# schematic.net
KiCad netlist of a schematic drawn in Altium Designer
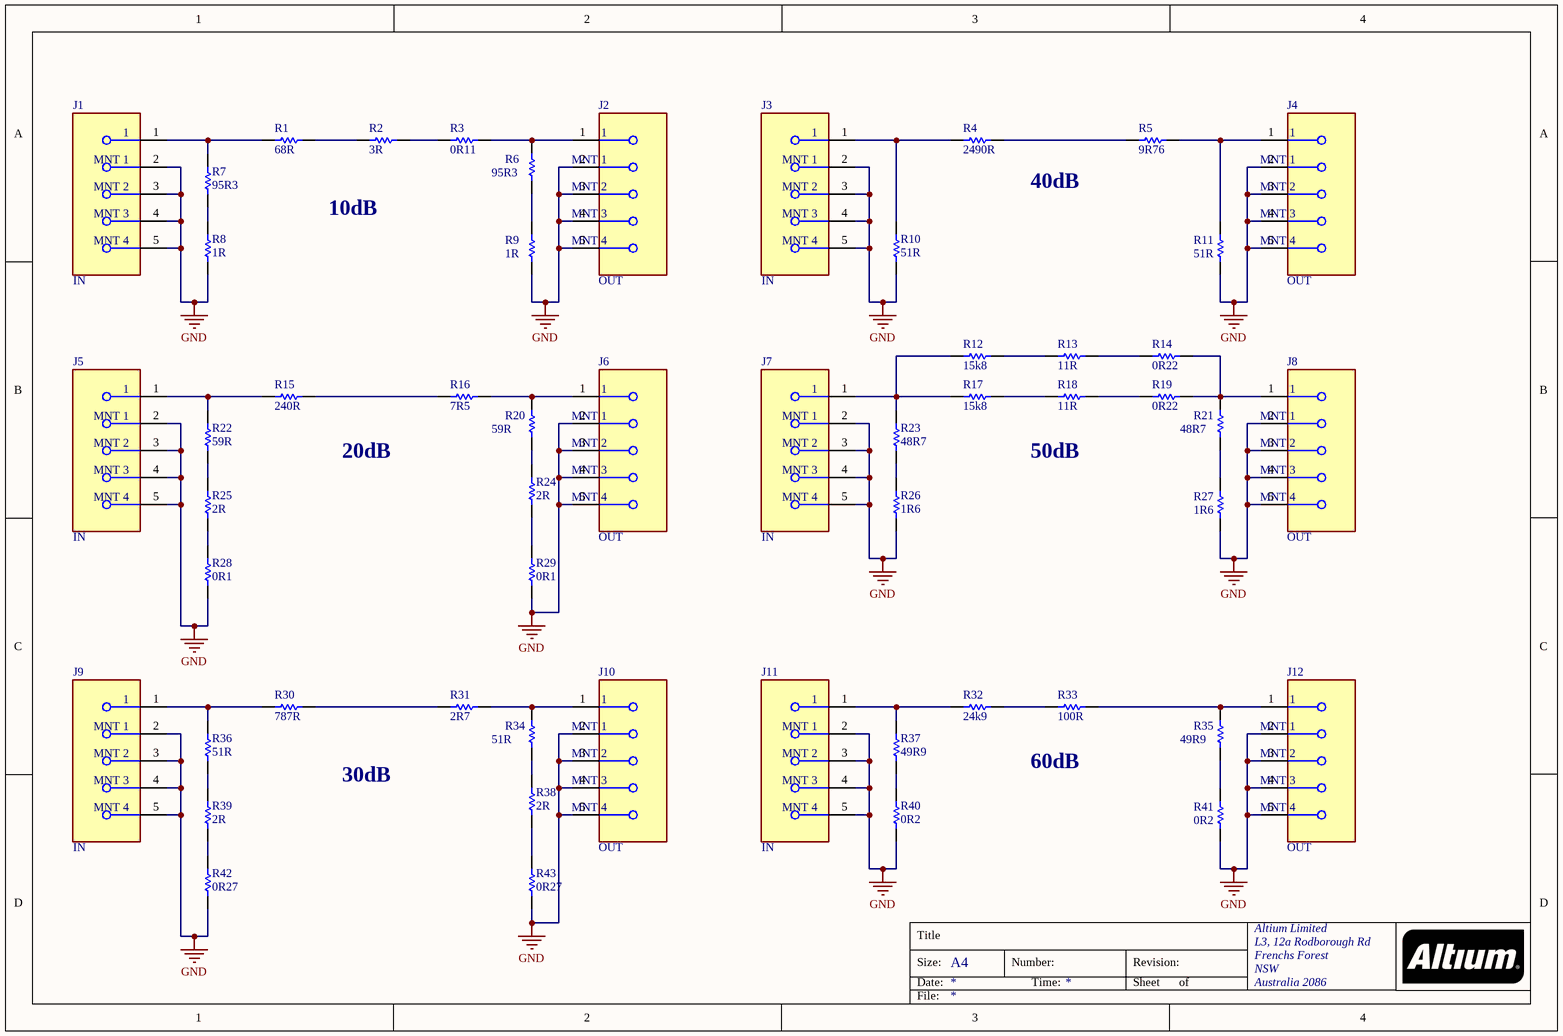
[diagram p0: schematic.SchDoc]

(export (version "E")
  (design (tool "Eeschema 10.0.6"))
  (components
    (comp (ref "J1")
      (value "IN")
      (footprint "FP-CON-SMA-EDGE-S-MFG")
      (description "CONN SMA JACK STR EDGE MNT")
      (fields
        (field (name "OCTOPART") "https://octopart.com/con-sma-edge-s-rf+solutions-70967450")
        (field (name "MANUFACTURER PART NUMBER") "CON-SMA-EDGE-S")
      )
      (libsource (lib "Altium Content Vault") (part "a163d97a771fcdd2fd1f1a9264c171f"))
    )
    (comp (ref "J2")
      (value "OUT")
      (footprint "FP-CON-SMA-EDGE-S-MFG")
      (description "CONN SMA JACK STR EDGE MNT")
      (fields
        (field (name "OCTOPART") "https://octopart.com/con-sma-edge-s-rf+solutions-70967450")
        (field (name "MANUFACTURER PART NUMBER") "CON-SMA-EDGE-S")
      )
      (libsource (lib "") (part "a163d97a771fcdd2fd1f1a9264c171f_1"))
    )
    (comp (ref "J3")
      (value "IN")
      (footprint "FP-CON-SMA-EDGE-S-MFG")
      (description "CONN SMA JACK STR EDGE MNT")
      (fields
        (field (name "OCTOPART") "https://octopart.com/con-sma-edge-s-rf+solutions-70967450")
        (field (name "MANUFACTURER PART NUMBER") "CON-SMA-EDGE-S")
      )
      (libsource (lib "Altium Content Vault") (part "a163d97a771fcdd2fd1f1a9264c171f"))
    )
    (comp (ref "J4")
      (value "OUT")
      (footprint "FP-CON-SMA-EDGE-S-MFG")
      (description "CONN SMA JACK STR EDGE MNT")
      (fields
        (field (name "OCTOPART") "https://octopart.com/con-sma-edge-s-rf+solutions-70967450")
        (field (name "MANUFACTURER PART NUMBER") "CON-SMA-EDGE-S")
      )
      (libsource (lib "") (part "a163d97a771fcdd2fd1f1a9264c171f_1"))
    )
    (comp (ref "J5")
      (value "IN")
      (footprint "FP-CON-SMA-EDGE-S-MFG")
      (description "CONN SMA JACK STR EDGE MNT")
      (fields
        (field (name "OCTOPART") "https://octopart.com/con-sma-edge-s-rf+solutions-70967450")
        (field (name "MANUFACTURER PART NUMBER") "CON-SMA-EDGE-S")
      )
      (libsource (lib "Altium Content Vault") (part "a163d97a771fcdd2fd1f1a9264c171f"))
    )
    (comp (ref "J6")
      (value "OUT")
      (footprint "FP-CON-SMA-EDGE-S-MFG")
      (description "CONN SMA JACK STR EDGE MNT")
      (fields
        (field (name "OCTOPART") "https://octopart.com/con-sma-edge-s-rf+solutions-70967450")
        (field (name "MANUFACTURER PART NUMBER") "CON-SMA-EDGE-S")
      )
      (libsource (lib "") (part "a163d97a771fcdd2fd1f1a9264c171f_1"))
    )
    (comp (ref "J7")
      (value "IN")
      (footprint "FP-CON-SMA-EDGE-S-MFG")
      (description "CONN SMA JACK STR EDGE MNT")
      (fields
        (field (name "OCTOPART") "https://octopart.com/con-sma-edge-s-rf+solutions-70967450")
        (field (name "MANUFACTURER PART NUMBER") "CON-SMA-EDGE-S")
      )
      (libsource (lib "Altium Content Vault") (part "a163d97a771fcdd2fd1f1a9264c171f"))
    )
    (comp (ref "J8")
      (value "OUT")
      (footprint "FP-CON-SMA-EDGE-S-MFG")
      (description "CONN SMA JACK STR EDGE MNT")
      (fields
        (field (name "OCTOPART") "https://octopart.com/con-sma-edge-s-rf+solutions-70967450")
        (field (name "MANUFACTURER PART NUMBER") "CON-SMA-EDGE-S")
      )
      (libsource (lib "") (part "a163d97a771fcdd2fd1f1a9264c171f_1"))
    )
    (comp (ref "J9")
      (value "IN")
      (footprint "FP-CON-SMA-EDGE-S-MFG")
      (description "CONN SMA JACK STR EDGE MNT")
      (fields
        (field (name "OCTOPART") "https://octopart.com/con-sma-edge-s-rf+solutions-70967450")
        (field (name "MANUFACTURER PART NUMBER") "CON-SMA-EDGE-S")
      )
      (libsource (lib "Altium Content Vault") (part "a163d97a771fcdd2fd1f1a9264c171f"))
    )
    (comp (ref "J10")
      (value "OUT")
      (footprint "FP-CON-SMA-EDGE-S-MFG")
      (description "CONN SMA JACK STR EDGE MNT")
      (fields
        (field (name "OCTOPART") "https://octopart.com/con-sma-edge-s-rf+solutions-70967450")
        (field (name "MANUFACTURER PART NUMBER") "CON-SMA-EDGE-S")
      )
      (libsource (lib "") (part "a163d97a771fcdd2fd1f1a9264c171f_1"))
    )
    (comp (ref "J11")
      (value "IN")
      (footprint "FP-CON-SMA-EDGE-S-MFG")
      (description "CONN SMA JACK STR EDGE MNT")
      (fields
        (field (name "OCTOPART") "https://octopart.com/con-sma-edge-s-rf+solutions-70967450")
        (field (name "MANUFACTURER PART NUMBER") "CON-SMA-EDGE-S")
      )
      (libsource (lib "Altium Content Vault") (part "a163d97a771fcdd2fd1f1a9264c171f"))
    )
    (comp (ref "J12")
      (value "OUT")
      (footprint "FP-CON-SMA-EDGE-S-MFG")
      (description "CONN SMA JACK STR EDGE MNT")
      (fields
        (field (name "OCTOPART") "https://octopart.com/con-sma-edge-s-rf+solutions-70967450")
        (field (name "MANUFACTURER PART NUMBER") "CON-SMA-EDGE-S")
      )
      (libsource (lib "") (part "a163d97a771fcdd2fd1f1a9264c171f_1"))
    )
    (comp (ref "R1")
      (value "68R")
      (footprint "RESC3225X70X50NL20T20")
      (fields (field (name "MANUFACTURER") "Panasonic") (field (name "PART NUMBER") "ERJ-14NF1001U"))
      (libsource (lib "Altium Content Vault") (part "RES"))
    )
    (comp (ref "R2")
      (value "3R")
      (footprint "RESC3225X70X50NL20T20")
      (fields (field (name "MANUFACTURER") "Panasonic") (field (name "PART NUMBER") "ERJ-14NF1001U"))
      (libsource (lib "Altium Content Vault") (part "RES"))
    )
    (comp (ref "R3")
      (value "0R11")
      (footprint "RESC3225X70X50NL20T20")
      (fields (field (name "MANUFACTURER") "Panasonic") (field (name "PART NUMBER") "ERJ-14NF1001U"))
      (libsource (lib "Altium Content Vault") (part "RES"))
    )
    (comp (ref "R4")
      (value "2490R")
      (footprint "RESC3225X70X50NL20T20")
      (fields (field (name "MANUFACTURER") "Panasonic") (field (name "PART NUMBER") "ERJ-14NF1001U"))
      (libsource (lib "Altium Content Vault") (part "RES"))
    )
    (comp (ref "R5")
      (value "9R76")
      (footprint "RESC3225X70X50NL20T20")
      (fields (field (name "MANUFACTURER") "Panasonic") (field (name "PART NUMBER") "ERJ-14NF1001U"))
      (libsource (lib "Altium Content Vault") (part "RES"))
    )
    (comp (ref "R6")
      (value "95R3")
      (footprint "RESC3225X70X50NL20T20")
      (fields (field (name "MANUFACTURER") "Panasonic") (field (name "PART NUMBER") "ERJ-14NF1001U"))
      (libsource (lib "Altium Content Vault") (part "RES"))
    )
    (comp (ref "R7")
      (value "95R3")
      (footprint "RESC3225X70X50NL20T20")
      (fields (field (name "MANUFACTURER") "Panasonic") (field (name "PART NUMBER") "ERJ-14NF1001U"))
      (libsource (lib "Altium Content Vault") (part "RES"))
    )
    (comp (ref "R8")
      (value "1R")
      (footprint "RESC3225X70X50NL20T20")
      (fields (field (name "MANUFACTURER") "Panasonic") (field (name "PART NUMBER") "ERJ-14NF1001U"))
      (libsource (lib "Altium Content Vault") (part "RES"))
    )
    (comp (ref "R9")
      (value "1R")
      (footprint "RESC3225X70X50NL20T20")
      (fields (field (name "MANUFACTURER") "Panasonic") (field (name "PART NUMBER") "ERJ-14NF1001U"))
      (libsource (lib "Altium Content Vault") (part "RES"))
    )
    (comp (ref "R10")
      (value "51R")
      (footprint "RESC3225X70X50NL20T20")
      (fields (field (name "MANUFACTURER") "Panasonic") (field (name "PART NUMBER") "ERJ-14NF1001U"))
      (libsource (lib "Altium Content Vault") (part "RES"))
    )
    (comp (ref "R11")
      (value "51R")
      (footprint "RESC3225X70X50NL20T20")
      (fields (field (name "MANUFACTURER") "Panasonic") (field (name "PART NUMBER") "ERJ-14NF1001U"))
      (libsource (lib "Altium Content Vault") (part "RES"))
    )
    (comp (ref "R12")
      (value "15k8")
      (footprint "RESC3225X70X50NL20T20")
      (fields (field (name "MANUFACTURER") "Panasonic") (field (name "PART NUMBER") "ERJ-14NF1001U"))
      (libsource (lib "Altium Content Vault") (part "RES"))
    )
    (comp (ref "R13")
      (value "11R")
      (footprint "RESC3225X70X50NL20T20")
      (fields (field (name "MANUFACTURER") "Panasonic") (field (name "PART NUMBER") "ERJ-14NF1001U"))
      (libsource (lib "Altium Content Vault") (part "RES"))
    )
    (comp (ref "R14")
      (value "0R22")
      (footprint "RESC3225X70X50NL20T20")
      (fields (field (name "MANUFACTURER") "Panasonic") (field (name "PART NUMBER") "ERJ-14NF1001U"))
      (libsource (lib "Altium Content Vault") (part "RES"))
    )
    (comp (ref "R15")
      (value "240R")
      (footprint "RESC3225X70X50NL20T20")
      (fields (field (name "MANUFACTURER") "Panasonic") (field (name "PART NUMBER") "ERJ-14NF1001U"))
      (libsource (lib "Altium Content Vault") (part "RES"))
    )
    (comp (ref "R16")
      (value "7R5")
      (footprint "RESC3225X70X50NL20T20")
      (fields (field (name "MANUFACTURER") "Panasonic") (field (name "PART NUMBER") "ERJ-14NF1001U"))
      (libsource (lib "Altium Content Vault") (part "RES"))
    )
    (comp (ref "R17")
      (value "15k8")
      (footprint "RESC3225X70X50NL20T20")
      (fields (field (name "MANUFACTURER") "Panasonic") (field (name "PART NUMBER") "ERJ-14NF1001U"))
      (libsource (lib "Altium Content Vault") (part "RES"))
    )
    (comp (ref "R18")
      (value "11R")
      (footprint "RESC3225X70X50NL20T20")
      (fields (field (name "MANUFACTURER") "Panasonic") (field (name "PART NUMBER") "ERJ-14NF1001U"))
      (libsource (lib "Altium Content Vault") (part "RES"))
    )
    (comp (ref "R19")
      (value "0R22")
      (footprint "RESC3225X70X50NL20T20")
      (fields (field (name "MANUFACTURER") "Panasonic") (field (name "PART NUMBER") "ERJ-14NF1001U"))
      (libsource (lib "Altium Content Vault") (part "RES"))
    )
    (comp (ref "R20")
      (value "59R")
      (footprint "RESC3225X70X50NL20T20")
      (fields (field (name "MANUFACTURER") "Panasonic") (field (name "PART NUMBER") "ERJ-14NF1001U"))
      (libsource (lib "Altium Content Vault") (part "RES"))
    )
    (comp (ref "R21")
      (value "48R7")
      (footprint "RESC3225X70X50NL20T20")
      (fields (field (name "MANUFACTURER") "Panasonic") (field (name "PART NUMBER") "ERJ-14NF1001U"))
      (libsource (lib "Altium Content Vault") (part "RES"))
    )
    (comp (ref "R22")
      (value "59R")
      (footprint "RESC3225X70X50NL20T20")
      (fields (field (name "MANUFACTURER") "Panasonic") (field (name "PART NUMBER") "ERJ-14NF1001U"))
      (libsource (lib "Altium Content Vault") (part "RES"))
    )
    (comp (ref "R23")
      (value "48R7")
      (footprint "RESC3225X70X50NL20T20")
      (fields (field (name "MANUFACTURER") "Panasonic") (field (name "PART NUMBER") "ERJ-14NF1001U"))
      (libsource (lib "Altium Content Vault") (part "RES"))
    )
    (comp (ref "R24")
      (value "2R")
      (footprint "RESC3225X70X50NL20T20")
      (fields (field (name "MANUFACTURER") "Panasonic") (field (name "PART NUMBER") "ERJ-14NF1001U"))
      (libsource (lib "Altium Content Vault") (part "RES"))
    )
    (comp (ref "R25")
      (value "2R")
      (footprint "RESC3225X70X50NL20T20")
      (fields (field (name "MANUFACTURER") "Panasonic") (field (name "PART NUMBER") "ERJ-14NF1001U"))
      (libsource (lib "Altium Content Vault") (part "RES"))
    )
    (comp (ref "R26")
      (value "1R6")
      (footprint "RESC3225X70X50NL20T20")
      (fields (field (name "MANUFACTURER") "Panasonic") (field (name "PART NUMBER") "ERJ-14NF1001U"))
      (libsource (lib "Altium Content Vault") (part "RES"))
    )
    (comp (ref "R27")
      (value "1R6")
      (footprint "RESC3225X70X50NL20T20")
      (fields (field (name "MANUFACTURER") "Panasonic") (field (name "PART NUMBER") "ERJ-14NF1001U"))
      (libsource (lib "Altium Content Vault") (part "RES"))
    )
    (comp (ref "R28")
      (value "0R1")
      (footprint "RESC3225X70X50NL20T20")
      (fields (field (name "MANUFACTURER") "Panasonic") (field (name "PART NUMBER") "ERJ-14NF1001U"))
      (libsource (lib "Altium Content Vault") (part "RES"))
    )
    (comp (ref "R29")
      (value "0R1")
      (footprint "RESC3225X70X50NL20T20")
      (fields (field (name "MANUFACTURER") "Panasonic") (field (name "PART NUMBER") "ERJ-14NF1001U"))
      (libsource (lib "Altium Content Vault") (part "RES"))
    )
    (comp (ref "R30")
      (value "787R")
      (footprint "RESC3225X70X50NL20T20")
      (fields (field (name "MANUFACTURER") "Panasonic") (field (name "PART NUMBER") "ERJ-14NF1001U"))
      (libsource (lib "Altium Content Vault") (part "RES"))
    )
    (comp (ref "R31")
      (value "2R7")
      (footprint "RESC3225X70X50NL20T20")
      (fields (field (name "MANUFACTURER") "Panasonic") (field (name "PART NUMBER") "ERJ-14NF1001U"))
      (libsource (lib "Altium Content Vault") (part "RES"))
    )
    (comp (ref "R32")
      (value "24k9")
      (footprint "RESC3225X70X50NL20T20")
      (fields (field (name "MANUFACTURER") "Panasonic") (field (name "PART NUMBER") "ERJ-14NF1001U"))
      (libsource (lib "Altium Content Vault") (part "RES"))
    )
    (comp (ref "R33")
      (value "100R")
      (footprint "RESC3225X70X50NL20T20")
      (fields (field (name "MANUFACTURER") "Panasonic") (field (name "PART NUMBER") "ERJ-14NF1001U"))
      (libsource (lib "Altium Content Vault") (part "RES"))
    )
    (comp (ref "R34")
      (value "51R")
      (footprint "RESC3225X70X50NL20T20")
      (fields (field (name "MANUFACTURER") "Panasonic") (field (name "PART NUMBER") "ERJ-14NF1001U"))
      (libsource (lib "Altium Content Vault") (part "RES"))
    )
    (comp (ref "R35")
      (value "49R9")
      (footprint "RESC3225X70X50NL20T20")
      (fields (field (name "MANUFACTURER") "Panasonic") (field (name "PART NUMBER") "ERJ-14NF1001U"))
      (libsource (lib "Altium Content Vault") (part "RES"))
    )
    (comp (ref "R36")
      (value "51R")
      (footprint "RESC3225X70X50NL20T20")
      (fields (field (name "MANUFACTURER") "Panasonic") (field (name "PART NUMBER") "ERJ-14NF1001U"))
      (libsource (lib "Altium Content Vault") (part "RES"))
    )
    (comp (ref "R37")
      (value "49R9")
      (footprint "RESC3225X70X50NL20T20")
      (fields (field (name "MANUFACTURER") "Panasonic") (field (name "PART NUMBER") "ERJ-14NF1001U"))
      (libsource (lib "Altium Content Vault") (part "RES"))
    )
    (comp (ref "R38")
      (value "2R")
      (footprint "RESC3225X70X50NL20T20")
      (fields (field (name "MANUFACTURER") "Panasonic") (field (name "PART NUMBER") "ERJ-14NF1001U"))
      (libsource (lib "Altium Content Vault") (part "RES"))
    )
    (comp (ref "R39")
      (value "2R")
      (footprint "RESC3225X70X50NL20T20")
      (fields (field (name "MANUFACTURER") "Panasonic") (field (name "PART NUMBER") "ERJ-14NF1001U"))
      (libsource (lib "Altium Content Vault") (part "RES"))
    )
    (comp (ref "R40")
      (value "0R2")
      (footprint "RESC3225X70X50NL20T20")
      (fields (field (name "MANUFACTURER") "Panasonic") (field (name "PART NUMBER") "ERJ-14NF1001U"))
      (libsource (lib "Altium Content Vault") (part "RES"))
    )
    (comp (ref "R41")
      (value "0R2")
      (footprint "RESC3225X70X50NL20T20")
      (fields (field (name "MANUFACTURER") "Panasonic") (field (name "PART NUMBER") "ERJ-14NF1001U"))
      (libsource (lib "Altium Content Vault") (part "RES"))
    )
    (comp (ref "R42")
      (value "0R27")
      (footprint "RESC3225X70X50NL20T20")
      (fields (field (name "MANUFACTURER") "Panasonic") (field (name "PART NUMBER") "ERJ-14NF1001U"))
      (libsource (lib "Altium Content Vault") (part "RES"))
    )
    (comp (ref "R43")
      (value "0R27")
      (footprint "RESC3225X70X50NL20T20")
      (fields (field (name "MANUFACTURER") "Panasonic") (field (name "PART NUMBER") "ERJ-14NF1001U"))
      (libsource (lib "Altium Content Vault") (part "RES"))
    )
  )
  (nets
    (net (code "1") (name "GND") (class "Default")
      (node (ref "J1") (pin "2") (pinfunction "MNT_1_2") (pintype "passive"))
      (node (ref "J1") (pin "3") (pinfunction "MNT_2_3") (pintype "passive"))
      (node (ref "J1") (pin "4") (pinfunction "MNT_3_4") (pintype "passive"))
      (node (ref "J1") (pin "5") (pinfunction "MNT_4_5") (pintype "passive"))
      (node (ref "J10") (pin "2") (pinfunction "MNT_1_2") (pintype "passive"))
      (node (ref "J10") (pin "3") (pinfunction "MNT_2_3") (pintype "passive"))
      (node (ref "J10") (pin "4") (pinfunction "MNT_3_4") (pintype "passive"))
      (node (ref "J10") (pin "5") (pinfunction "MNT_4_5") (pintype "passive"))
      (node (ref "J11") (pin "2") (pinfunction "MNT_1_2") (pintype "passive"))
      (node (ref "J11") (pin "3") (pinfunction "MNT_2_3") (pintype "passive"))
      (node (ref "J11") (pin "4") (pinfunction "MNT_3_4") (pintype "passive"))
      (node (ref "J11") (pin "5") (pinfunction "MNT_4_5") (pintype "passive"))
      (node (ref "J12") (pin "2") (pinfunction "MNT_1_2") (pintype "passive"))
      (node (ref "J12") (pin "3") (pinfunction "MNT_2_3") (pintype "passive"))
      (node (ref "J12") (pin "4") (pinfunction "MNT_3_4") (pintype "passive"))
      (node (ref "J12") (pin "5") (pinfunction "MNT_4_5") (pintype "passive"))
      (node (ref "J2") (pin "2") (pinfunction "MNT_1_2") (pintype "passive"))
      (node (ref "J2") (pin "3") (pinfunction "MNT_2_3") (pintype "passive"))
      (node (ref "J2") (pin "4") (pinfunction "MNT_3_4") (pintype "passive"))
      (node (ref "J2") (pin "5") (pinfunction "MNT_4_5") (pintype "passive"))
      (node (ref "J3") (pin "2") (pinfunction "MNT_1_2") (pintype "passive"))
      (node (ref "J3") (pin "3") (pinfunction "MNT_2_3") (pintype "passive"))
      (node (ref "J3") (pin "4") (pinfunction "MNT_3_4") (pintype "passive"))
      (node (ref "J3") (pin "5") (pinfunction "MNT_4_5") (pintype "passive"))
      (node (ref "J4") (pin "2") (pinfunction "MNT_1_2") (pintype "passive"))
      (node (ref "J4") (pin "3") (pinfunction "MNT_2_3") (pintype "passive"))
      (node (ref "J4") (pin "4") (pinfunction "MNT_3_4") (pintype "passive"))
      (node (ref "J4") (pin "5") (pinfunction "MNT_4_5") (pintype "passive"))
      (node (ref "J5") (pin "2") (pinfunction "MNT_1_2") (pintype "passive"))
      (node (ref "J5") (pin "3") (pinfunction "MNT_2_3") (pintype "passive"))
      (node (ref "J5") (pin "4") (pinfunction "MNT_3_4") (pintype "passive"))
      (node (ref "J5") (pin "5") (pinfunction "MNT_4_5") (pintype "passive"))
      (node (ref "J6") (pin "2") (pinfunction "MNT_1_2") (pintype "passive"))
      (node (ref "J6") (pin "3") (pinfunction "MNT_2_3") (pintype "passive"))
      (node (ref "J6") (pin "4") (pinfunction "MNT_3_4") (pintype "passive"))
      (node (ref "J6") (pin "5") (pinfunction "MNT_4_5") (pintype "passive"))
      (node (ref "J7") (pin "2") (pinfunction "MNT_1_2") (pintype "passive"))
      (node (ref "J7") (pin "3") (pinfunction "MNT_2_3") (pintype "passive"))
      (node (ref "J7") (pin "4") (pinfunction "MNT_3_4") (pintype "passive"))
      (node (ref "J7") (pin "5") (pinfunction "MNT_4_5") (pintype "passive"))
      (node (ref "J8") (pin "2") (pinfunction "MNT_1_2") (pintype "passive"))
      (node (ref "J8") (pin "3") (pinfunction "MNT_2_3") (pintype "passive"))
      (node (ref "J8") (pin "4") (pinfunction "MNT_3_4") (pintype "passive"))
      (node (ref "J8") (pin "5") (pinfunction "MNT_4_5") (pintype "passive"))
      (node (ref "J9") (pin "2") (pinfunction "MNT_1_2") (pintype "passive"))
      (node (ref "J9") (pin "3") (pinfunction "MNT_2_3") (pintype "passive"))
      (node (ref "J9") (pin "4") (pinfunction "MNT_3_4") (pintype "passive"))
      (node (ref "J9") (pin "5") (pinfunction "MNT_4_5") (pintype "passive"))
      (node (ref "R10") (pin "1") (pinfunction "1_1") (pintype "passive"))
      (node (ref "R11") (pin "1") (pinfunction "1_1") (pintype "passive"))
      (node (ref "R26") (pin "1") (pinfunction "1_1") (pintype "passive"))
      (node (ref "R27") (pin "1") (pinfunction "1_1") (pintype "passive"))
      (node (ref "R28") (pin "1") (pinfunction "1_1") (pintype "passive"))
      (node (ref "R29") (pin "1") (pinfunction "1_1") (pintype "passive"))
      (node (ref "R40") (pin "1") (pinfunction "1_1") (pintype "passive"))
      (node (ref "R41") (pin "1") (pinfunction "1_1") (pintype "passive"))
      (node (ref "R42") (pin "1") (pinfunction "1_1") (pintype "passive"))
      (node (ref "R43") (pin "1") (pinfunction "1_1") (pintype "passive"))
      (node (ref "R8") (pin "1") (pinfunction "1_1") (pintype "passive"))
      (node (ref "R9") (pin "1") (pinfunction "1_1") (pintype "passive"))
    )
    (net (code "2") (name "Net-(J1-Pad1)") (class "Default")
      (node (ref "J1") (pin "1") (pinfunction "1_1") (pintype "passive"))
      (node (ref "R1") (pin "1") (pinfunction "1_1") (pintype "passive"))
      (node (ref "R7") (pin "2") (pinfunction "2_2") (pintype "passive"))
    )
    (net (code "3") (name "Net-(J2-Pad1)") (class "Default")
      (node (ref "J2") (pin "1") (pinfunction "1_1") (pintype "passive"))
      (node (ref "R3") (pin "2") (pinfunction "2_2") (pintype "passive"))
      (node (ref "R6") (pin "2") (pinfunction "2_2") (pintype "passive"))
    )
    (net (code "4") (name "Net-(J3-Pad1)") (class "Default")
      (node (ref "J3") (pin "1") (pinfunction "1_1") (pintype "passive"))
      (node (ref "R10") (pin "2") (pinfunction "2_2") (pintype "passive"))
      (node (ref "R4") (pin "1") (pinfunction "1_1") (pintype "passive"))
    )
    (net (code "5") (name "Net-(J4-Pad1)") (class "Default")
      (node (ref "J4") (pin "1") (pinfunction "1_1") (pintype "passive"))
      (node (ref "R11") (pin "2") (pinfunction "2_2") (pintype "passive"))
      (node (ref "R5") (pin "2") (pinfunction "2_2") (pintype "passive"))
    )
    (net (code "6") (name "Net-(J5-Pad1)") (class "Default")
      (node (ref "J5") (pin "1") (pinfunction "1_1") (pintype "passive"))
      (node (ref "R15") (pin "1") (pinfunction "1_1") (pintype "passive"))
      (node (ref "R22") (pin "2") (pinfunction "2_2") (pintype "passive"))
    )
    (net (code "7") (name "Net-(J6-Pad1)") (class "Default")
      (node (ref "J6") (pin "1") (pinfunction "1_1") (pintype "passive"))
      (node (ref "R16") (pin "2") (pinfunction "2_2") (pintype "passive"))
      (node (ref "R20") (pin "2") (pinfunction "2_2") (pintype "passive"))
    )
    (net (code "8") (name "Net-(J7-Pad1)") (class "Default")
      (node (ref "J7") (pin "1") (pinfunction "1_1") (pintype "passive"))
      (node (ref "R12") (pin "1") (pinfunction "1_1") (pintype "passive"))
      (node (ref "R17") (pin "1") (pinfunction "1_1") (pintype "passive"))
      (node (ref "R23") (pin "2") (pinfunction "2_2") (pintype "passive"))
    )
    (net (code "9") (name "Net-(J8-Pad1)") (class "Default")
      (node (ref "J8") (pin "1") (pinfunction "1_1") (pintype "passive"))
      (node (ref "R14") (pin "2") (pinfunction "2_2") (pintype "passive"))
      (node (ref "R19") (pin "2") (pinfunction "2_2") (pintype "passive"))
      (node (ref "R21") (pin "2") (pinfunction "2_2") (pintype "passive"))
    )
    (net (code "10") (name "Net-(J9-Pad1)") (class "Default")
      (node (ref "J9") (pin "1") (pinfunction "1_1") (pintype "passive"))
      (node (ref "R30") (pin "1") (pinfunction "1_1") (pintype "passive"))
      (node (ref "R36") (pin "2") (pinfunction "2_2") (pintype "passive"))
    )
    (net (code "11") (name "Net-(J10-Pad1)") (class "Default")
      (node (ref "J10") (pin "1") (pinfunction "1_1") (pintype "passive"))
      (node (ref "R31") (pin "2") (pinfunction "2_2") (pintype "passive"))
      (node (ref "R34") (pin "2") (pinfunction "2_2") (pintype "passive"))
    )
    (net (code "12") (name "Net-(J11-Pad1)") (class "Default")
      (node (ref "J11") (pin "1") (pinfunction "1_1") (pintype "passive"))
      (node (ref "R32") (pin "1") (pinfunction "1_1") (pintype "passive"))
      (node (ref "R37") (pin "2") (pinfunction "2_2") (pintype "passive"))
    )
    (net (code "13") (name "Net-(J12-Pad1)") (class "Default")
      (node (ref "J12") (pin "1") (pinfunction "1_1") (pintype "passive"))
      (node (ref "R33") (pin "2") (pinfunction "2_2") (pintype "passive"))
      (node (ref "R35") (pin "2") (pinfunction "2_2") (pintype "passive"))
    )
    (net (code "14") (name "Net-(R1-Pad2)") (class "Default")
      (node (ref "R1") (pin "2") (pinfunction "2_2") (pintype "passive"))
      (node (ref "R2") (pin "1") (pinfunction "1_1") (pintype "passive"))
    )
    (net (code "15") (name "Net-(R2-Pad2)") (class "Default")
      (node (ref "R2") (pin "2") (pinfunction "2_2") (pintype "passive"))
      (node (ref "R3") (pin "1") (pinfunction "1_1") (pintype "passive"))
    )
    (net (code "16") (name "Net-(R4-Pad2)") (class "Default")
      (node (ref "R4") (pin "2") (pinfunction "2_2") (pintype "passive"))
      (node (ref "R5") (pin "1") (pinfunction "1_1") (pintype "passive"))
    )
    (net (code "17") (name "Net-(R6-Pad1)") (class "Default")
      (node (ref "R6") (pin "1") (pinfunction "1_1") (pintype "passive"))
      (node (ref "R9") (pin "2") (pinfunction "2_2") (pintype "passive"))
    )
    (net (code "18") (name "Net-(R7-Pad1)") (class "Default")
      (node (ref "R7") (pin "1") (pinfunction "1_1") (pintype "passive"))
      (node (ref "R8") (pin "2") (pinfunction "2_2") (pintype "passive"))
    )
    (net (code "19") (name "Net-(R12-Pad2)") (class "Default")
      (node (ref "R12") (pin "2") (pinfunction "2_2") (pintype "passive"))
      (node (ref "R13") (pin "1") (pinfunction "1_1") (pintype "passive"))
    )
    (net (code "20") (name "Net-(R13-Pad2)") (class "Default")
      (node (ref "R13") (pin "2") (pinfunction "2_2") (pintype "passive"))
      (node (ref "R14") (pin "1") (pinfunction "1_1") (pintype "passive"))
    )
    (net (code "21") (name "Net-(R15-Pad2)") (class "Default")
      (node (ref "R15") (pin "2") (pinfunction "2_2") (pintype "passive"))
      (node (ref "R16") (pin "1") (pinfunction "1_1") (pintype "passive"))
    )
    (net (code "22") (name "Net-(R17-Pad2)") (class "Default")
      (node (ref "R17") (pin "2") (pinfunction "2_2") (pintype "passive"))
      (node (ref "R18") (pin "1") (pinfunction "1_1") (pintype "passive"))
    )
    (net (code "23") (name "Net-(R18-Pad2)") (class "Default")
      (node (ref "R18") (pin "2") (pinfunction "2_2") (pintype "passive"))
      (node (ref "R19") (pin "1") (pinfunction "1_1") (pintype "passive"))
    )
    (net (code "24") (name "Net-(R20-Pad1)") (class "Default")
      (node (ref "R20") (pin "1") (pinfunction "1_1") (pintype "passive"))
      (node (ref "R24") (pin "2") (pinfunction "2_2") (pintype "passive"))
    )
    (net (code "25") (name "Net-(R21-Pad1)") (class "Default")
      (node (ref "R21") (pin "1") (pinfunction "1_1") (pintype "passive"))
      (node (ref "R27") (pin "2") (pinfunction "2_2") (pintype "passive"))
    )
    (net (code "26") (name "Net-(R22-Pad1)") (class "Default")
      (node (ref "R22") (pin "1") (pinfunction "1_1") (pintype "passive"))
      (node (ref "R25") (pin "2") (pinfunction "2_2") (pintype "passive"))
    )
    (net (code "27") (name "Net-(R23-Pad1)") (class "Default")
      (node (ref "R23") (pin "1") (pinfunction "1_1") (pintype "passive"))
      (node (ref "R26") (pin "2") (pinfunction "2_2") (pintype "passive"))
    )
    (net (code "28") (name "Net-(R24-Pad1)") (class "Default")
      (node (ref "R24") (pin "1") (pinfunction "1_1") (pintype "passive"))
      (node (ref "R29") (pin "2") (pinfunction "2_2") (pintype "passive"))
    )
    (net (code "29") (name "Net-(R25-Pad1)") (class "Default")
      (node (ref "R25") (pin "1") (pinfunction "1_1") (pintype "passive"))
      (node (ref "R28") (pin "2") (pinfunction "2_2") (pintype "passive"))
    )
    (net (code "30") (name "Net-(R30-Pad2)") (class "Default")
      (node (ref "R30") (pin "2") (pinfunction "2_2") (pintype "passive"))
      (node (ref "R31") (pin "1") (pinfunction "1_1") (pintype "passive"))
    )
    (net (code "31") (name "Net-(R32-Pad2)") (class "Default")
      (node (ref "R32") (pin "2") (pinfunction "2_2") (pintype "passive"))
      (node (ref "R33") (pin "1") (pinfunction "1_1") (pintype "passive"))
    )
    (net (code "32") (name "Net-(R34-Pad1)") (class "Default")
      (node (ref "R34") (pin "1") (pinfunction "1_1") (pintype "passive"))
      (node (ref "R38") (pin "2") (pinfunction "2_2") (pintype "passive"))
    )
    (net (code "33") (name "Net-(R35-Pad1)") (class "Default")
      (node (ref "R35") (pin "1") (pinfunction "1_1") (pintype "passive"))
      (node (ref "R41") (pin "2") (pinfunction "2_2") (pintype "passive"))
    )
    (net (code "34") (name "Net-(R36-Pad1)") (class "Default")
      (node (ref "R36") (pin "1") (pinfunction "1_1") (pintype "passive"))
      (node (ref "R39") (pin "2") (pinfunction "2_2") (pintype "passive"))
    )
    (net (code "35") (name "Net-(R37-Pad1)") (class "Default")
      (node (ref "R37") (pin "1") (pinfunction "1_1") (pintype "passive"))
      (node (ref "R40") (pin "2") (pinfunction "2_2") (pintype "passive"))
    )
    (net (code "36") (name "Net-(R38-Pad1)") (class "Default")
      (node (ref "R38") (pin "1") (pinfunction "1_1") (pintype "passive"))
      (node (ref "R43") (pin "2") (pinfunction "2_2") (pintype "passive"))
    )
    (net (code "37") (name "Net-(R39-Pad1)") (class "Default")
      (node (ref "R39") (pin "1") (pinfunction "1_1") (pintype "passive"))
      (node (ref "R42") (pin "2") (pinfunction "2_2") (pintype "passive"))
    )
  )
)
